# PhasedArrayReceiver1.net
KiCad netlist of a schematic drawn in EAGLE
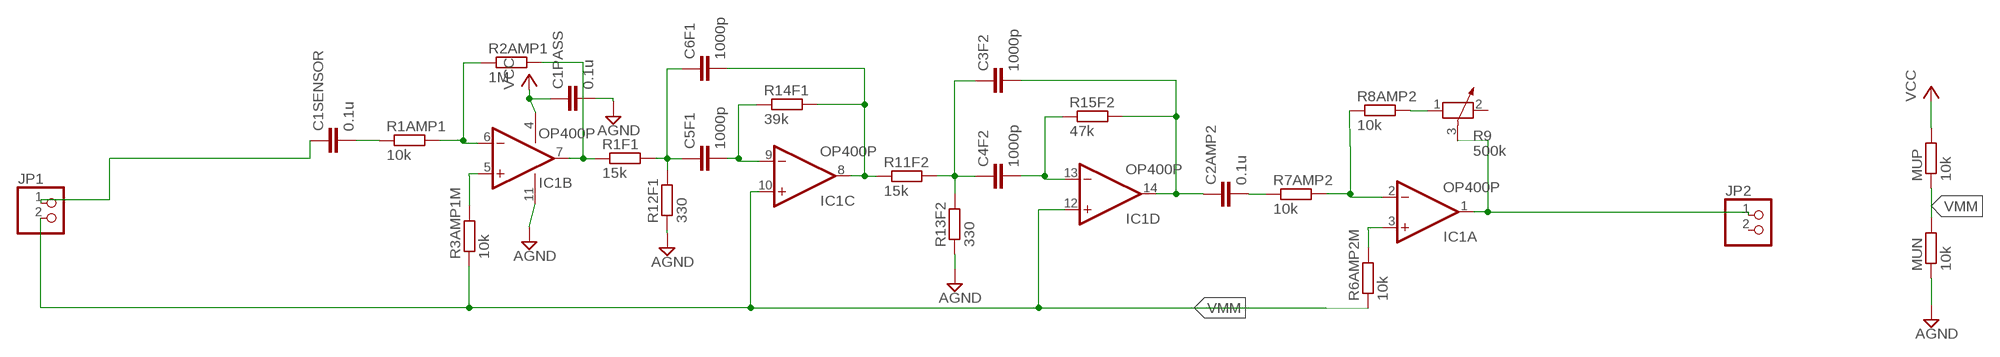
[diagram p0: schematic, sheet 1]

(export (version "E")
  (design (tool "Eeschema 10.0.6"))
  (components
    (comp (ref "C1PASS")
      (value "0.1u")
      (footprint "eagle-import:C025-024X044")
      (libsource (lib "eagle-import") (part "C-EU025-024X044"))
    )
    (comp (ref "C1SENSOR")
      (value "0.1u")
      (footprint "eagle-import:C0603K")
      (libsource (lib "eagle-import") (part "C-EUC0603K"))
    )
    (comp (ref "C2AMP2")
      (value "0.1u")
      (footprint "eagle-import:C0603K")
      (libsource (lib "eagle-import") (part "C-EUC0603K"))
    )
    (comp (ref "C3F2")
      (value "1000p")
      (footprint "eagle-import:C0603K")
      (libsource (lib "eagle-import") (part "C-EUC0603K"))
    )
    (comp (ref "C4F2")
      (value "1000p")
      (footprint "eagle-import:C0603K")
      (libsource (lib "eagle-import") (part "C-EUC0603K"))
    )
    (comp (ref "C5F1")
      (value "1000p")
      (footprint "eagle-import:C0603K")
      (libsource (lib "eagle-import") (part "C-EUC0603K"))
    )
    (comp (ref "C6F1")
      (value "1000p")
      (footprint "eagle-import:C0603K")
      (libsource (lib "eagle-import") (part "C-EUC0603K"))
    )
    (comp (ref "IC1")
      (value "OP400P")
      (footprint "eagle-import:DIL14")
      (libsource (lib "eagle-import") (part "OP400P"))
    )
    (comp (ref "JP1")
      (value "PINHD-1X2")
      (footprint "eagle-import:1X02")
      (libsource (lib "eagle-import") (part "PINHD-1X2"))
    )
    (comp (ref "JP2")
      (value "PINHD-1X2")
      (footprint "eagle-import:1X02")
      (libsource (lib "eagle-import") (part "PINHD-1X2"))
    )
    (comp (ref "MUN")
      (value "10k")
      (footprint "eagle-import:0207_7")
      (libsource (lib "eagle-import") (part "R-EU_0207/7"))
    )
    (comp (ref "MUP")
      (value "10k")
      (footprint "eagle-import:0207_7")
      (libsource (lib "eagle-import") (part "R-EU_0207/7"))
    )
    (comp (ref "R1AMP1")
      (value "10k")
      (footprint "eagle-import:R0603")
      (libsource (lib "eagle-import") (part "R-EU_R0603"))
    )
    (comp (ref "R1F1")
      (value "15k")
      (footprint "eagle-import:0207_7")
      (libsource (lib "eagle-import") (part "R-EU_0207/7"))
    )
    (comp (ref "R2AMP1")
      (value "1M")
      (footprint "eagle-import:R0603")
      (libsource (lib "eagle-import") (part "R-EU_R0603"))
    )
    (comp (ref "R3AMP1M")
      (value "10k")
      (footprint "eagle-import:R0603")
      (libsource (lib "eagle-import") (part "R-EU_R0603"))
    )
    (comp (ref "R6AMP2M")
      (value "10k")
      (footprint "eagle-import:R0603")
      (libsource (lib "eagle-import") (part "R-EU_R0603"))
    )
    (comp (ref "R7AMP2")
      (value "10k")
      (footprint "eagle-import:R0603")
      (libsource (lib "eagle-import") (part "R-EU_R0603"))
    )
    (comp (ref "R8AMP2")
      (value "10k")
      (footprint "eagle-import:R0603")
      (libsource (lib "eagle-import") (part "R-EU_R0603"))
    )
    (comp (ref "R9")
      (value "500k")
      (footprint "eagle-import:PT-10")
      (libsource (lib "eagle-import") (part "POTENTIOMETER_PT-10"))
    )
    (comp (ref "R11F2")
      (value "15k")
      (footprint "eagle-import:R0603")
      (libsource (lib "eagle-import") (part "R-EU_R0603"))
    )
    (comp (ref "R12F1")
      (value "330")
      (footprint "eagle-import:R0603")
      (libsource (lib "eagle-import") (part "R-EU_R0603"))
    )
    (comp (ref "R13F2")
      (value "330")
      (footprint "eagle-import:R0603")
      (libsource (lib "eagle-import") (part "R-EU_R0603"))
    )
    (comp (ref "R14F1")
      (value "39k")
      (footprint "eagle-import:0207_7")
      (libsource (lib "eagle-import") (part "R-EU_0207/7"))
    )
    (comp (ref "R15F2")
      (value "47k")
      (footprint "eagle-import:0207_7")
      (libsource (lib "eagle-import") (part "R-EU_0207/7"))
    )
  )
  (nets
    (net (code "1") (name "AGND") (class "Default")
      (node (ref "C1PASS") (pin "2") (pinfunction "2_2") (pintype "passive"))
      (node (ref "IC1") (pin "11") (pinfunction "V-_11") (pintype "power_in"))
      (node (ref "MUN") (pin "1") (pinfunction "1_1") (pintype "passive"))
      (node (ref "R12F1") (pin "1") (pinfunction "1_1") (pintype "passive"))
      (node (ref "R13F2") (pin "1") (pinfunction "1_1") (pintype "passive"))
    )
    (net (code "2") (name "Net-(C1SENSOR-Pad1)") (class "Default")
      (node (ref "C1SENSOR") (pin "1") (pinfunction "1_1") (pintype "passive"))
      (node (ref "JP1") (pin "1") (pinfunction "1_1") (pintype "passive"))
    )
    (net (code "3") (name "Net-(C1SENSOR-Pad2)") (class "Default")
      (node (ref "C1SENSOR") (pin "2") (pinfunction "2_2") (pintype "passive"))
      (node (ref "R1AMP1") (pin "1") (pinfunction "1_1") (pintype "passive"))
    )
    (net (code "4") (name "Net-(C2AMP2-Pad2)") (class "Default")
      (node (ref "C2AMP2") (pin "2") (pinfunction "2_2") (pintype "passive"))
      (node (ref "R7AMP2") (pin "1") (pinfunction "1_1") (pintype "passive"))
    )
    (net (code "5") (name "Net-(C3F2-Pad1)") (class "Default")
      (node (ref "C3F2") (pin "1") (pinfunction "1_1") (pintype "passive"))
      (node (ref "C4F2") (pin "1") (pinfunction "1_1") (pintype "passive"))
      (node (ref "R11F2") (pin "2") (pinfunction "2_2") (pintype "passive"))
      (node (ref "R13F2") (pin "2") (pinfunction "2_2") (pintype "passive"))
    )
    (net (code "6") (name "Net-(C5F1-Pad1)") (class "Default")
      (node (ref "C5F1") (pin "1") (pinfunction "1_1") (pintype "passive"))
      (node (ref "C6F1") (pin "1") (pinfunction "1_1") (pintype "passive"))
      (node (ref "R12F1") (pin "2") (pinfunction "2_2") (pintype "passive"))
      (node (ref "R1F1") (pin "2") (pinfunction "2_2") (pintype "passive"))
    )
    (net (code "7") (name "Net-(IC1A-+IN)") (class "Default")
      (node (ref "IC1") (pin "3") (pinfunction "+IN_3") (pintype "input"))
      (node (ref "R6AMP2M") (pin "2") (pinfunction "2_2") (pintype "passive"))
    )
    (net (code "8") (name "Net-(IC1A--IN)") (class "Default")
      (node (ref "IC1") (pin "2") (pinfunction "-IN_2") (pintype "input"))
      (node (ref "R7AMP2") (pin "2") (pinfunction "2_2") (pintype "passive"))
      (node (ref "R8AMP2") (pin "1") (pinfunction "1_1") (pintype "passive"))
    )
    (net (code "9") (name "Net-(IC1A-OUT)") (class "Default")
      (node (ref "IC1") (pin "1") (pinfunction "OUT_1") (pintype "output"))
      (node (ref "JP2") (pin "1") (pinfunction "1_1") (pintype "passive"))
      (node (ref "R9") (pin "3") (pinfunction "3_3") (pintype "passive"))
    )
    (net (code "10") (name "Net-(IC1B-+IN)") (class "Default")
      (node (ref "IC1") (pin "5") (pinfunction "+IN_5") (pintype "input"))
      (node (ref "R3AMP1M") (pin "2") (pinfunction "2_2") (pintype "passive"))
    )
    (net (code "11") (name "Net-(IC1B--IN)") (class "Default")
      (node (ref "IC1") (pin "6") (pinfunction "-IN_6") (pintype "input"))
      (node (ref "R1AMP1") (pin "2") (pinfunction "2_2") (pintype "passive"))
      (node (ref "R2AMP1") (pin "1") (pinfunction "1_1") (pintype "passive"))
    )
    (net (code "12") (name "Net-(IC1B-OUT)") (class "Default")
      (node (ref "IC1") (pin "7") (pinfunction "OUT_7") (pintype "output"))
      (node (ref "R1F1") (pin "1") (pinfunction "1_1") (pintype "passive"))
      (node (ref "R2AMP1") (pin "2") (pinfunction "2_2") (pintype "passive"))
    )
    (net (code "13") (name "Net-(IC1C--IN)") (class "Default")
      (node (ref "C5F1") (pin "2") (pinfunction "2_2") (pintype "passive"))
      (node (ref "IC1") (pin "9") (pinfunction "-IN_9") (pintype "input"))
      (node (ref "R14F1") (pin "1") (pinfunction "1_1") (pintype "passive"))
    )
    (net (code "14") (name "Net-(IC1C-OUT)") (class "Default")
      (node (ref "C6F1") (pin "2") (pinfunction "2_2") (pintype "passive"))
      (node (ref "IC1") (pin "8") (pinfunction "OUT_8") (pintype "output"))
      (node (ref "R11F2") (pin "1") (pinfunction "1_1") (pintype "passive"))
      (node (ref "R14F1") (pin "2") (pinfunction "2_2") (pintype "passive"))
    )
    (net (code "15") (name "Net-(IC1D--IN)") (class "Default")
      (node (ref "C4F2") (pin "2") (pinfunction "2_2") (pintype "passive"))
      (node (ref "IC1") (pin "13") (pinfunction "-IN_13") (pintype "input"))
      (node (ref "R15F2") (pin "1") (pinfunction "1_1") (pintype "passive"))
    )
    (net (code "16") (name "Net-(IC1D-OUT)") (class "Default")
      (node (ref "C2AMP2") (pin "1") (pinfunction "1_1") (pintype "passive"))
      (node (ref "C3F2") (pin "2") (pinfunction "2_2") (pintype "passive"))
      (node (ref "IC1") (pin "14") (pinfunction "OUT_14") (pintype "output"))
      (node (ref "R15F2") (pin "2") (pinfunction "2_2") (pintype "passive"))
    )
    (net (code "17") (name "Net-(R8AMP2-Pad2)") (class "Default")
      (node (ref "R8AMP2") (pin "2") (pinfunction "2_2") (pintype "passive"))
      (node (ref "R9") (pin "1") (pinfunction "1_1") (pintype "passive"))
    )
    (net (code "18") (name "VCC") (class "Default")
      (node (ref "C1PASS") (pin "1") (pinfunction "1_1") (pintype "passive"))
      (node (ref "IC1") (pin "4") (pinfunction "V+_4") (pintype "power_in"))
      (node (ref "MUP") (pin "2") (pinfunction "2_2") (pintype "passive"))
    )
    (net (code "19") (name "VMM") (class "Default")
      (node (ref "IC1") (pin "10") (pinfunction "+IN_10") (pintype "input"))
      (node (ref "IC1") (pin "12") (pinfunction "+IN_12") (pintype "input"))
      (node (ref "JP1") (pin "2") (pinfunction "2_2") (pintype "passive"))
      (node (ref "MUN") (pin "2") (pinfunction "2_2") (pintype "passive"))
      (node (ref "MUP") (pin "1") (pinfunction "1_1") (pintype "passive"))
      (node (ref "R3AMP1M") (pin "1") (pinfunction "1_1") (pintype "passive"))
      (node (ref "R6AMP2M") (pin "1") (pinfunction "1_1") (pintype "passive"))
    )
    (net (code "20") (name "unconnected-(JP2-Pad2)") (class "Default")
      (node (ref "JP2") (pin "2") (pinfunction "2_2") (pintype "passive"))
    )
    (net (code "21") (name "unconnected-(R9-Pad2)") (class "Default")
      (node (ref "R9") (pin "2") (pinfunction "2_2") (pintype "passive"))
    )
  )
)
